# DM2097_CM4.net
KiCad netlist of a schematic drawn in Altium Designer
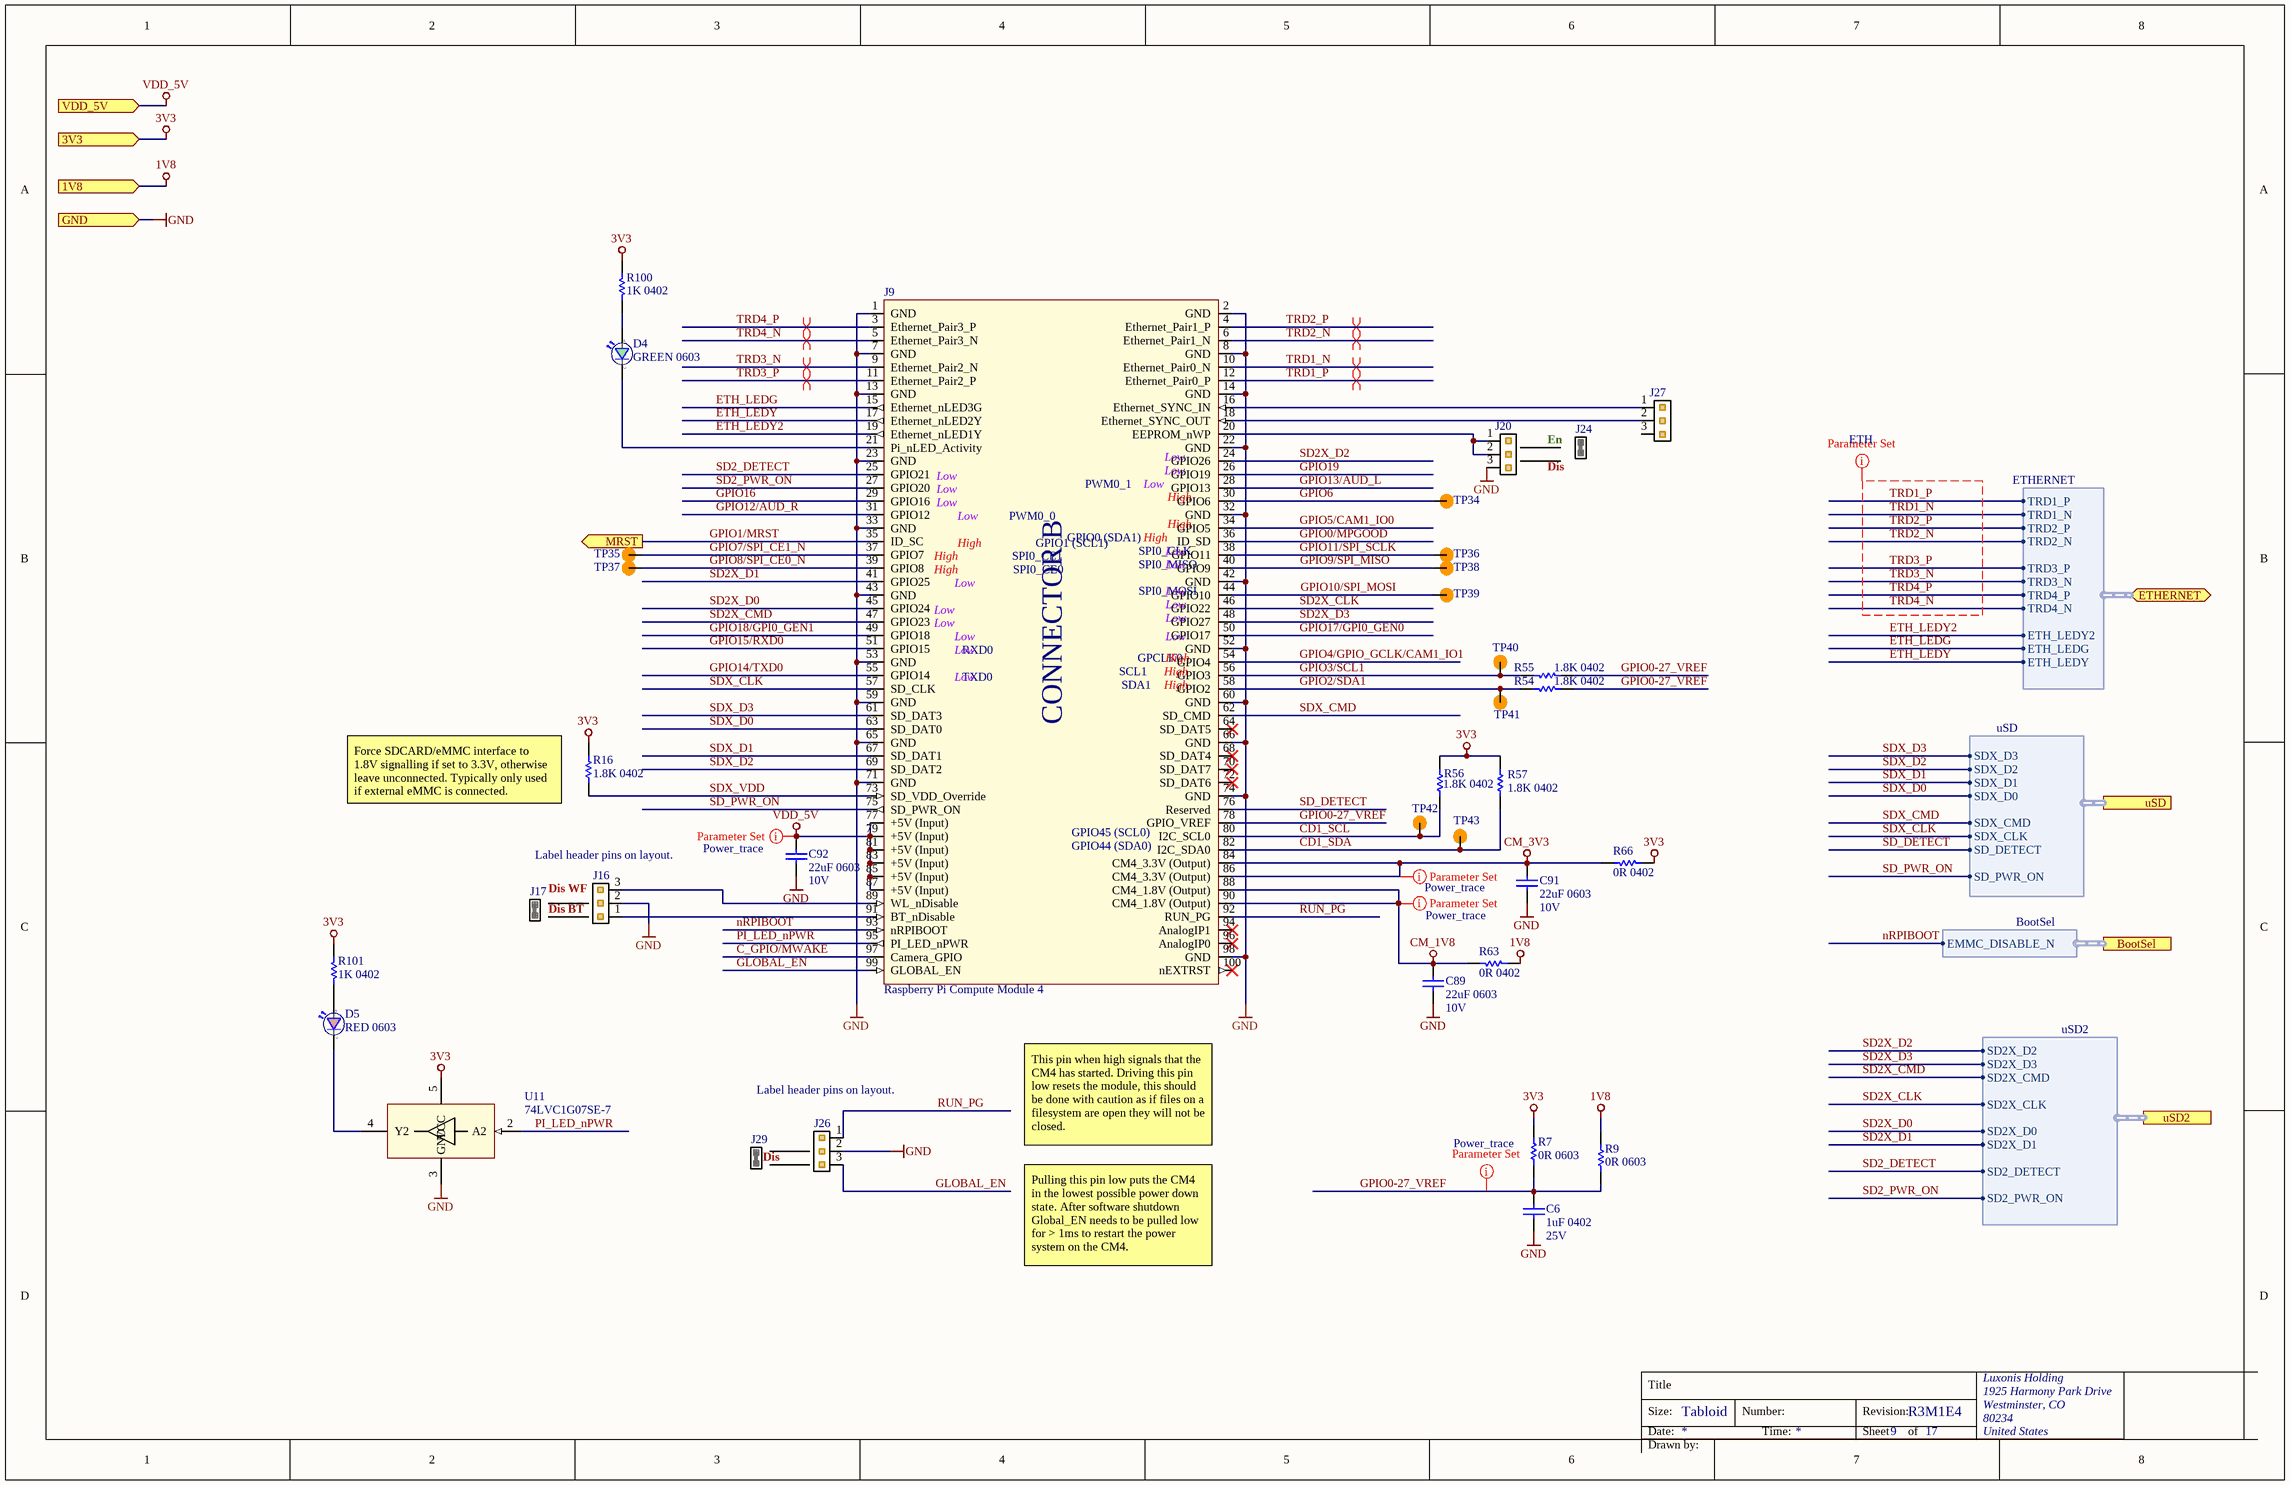
[diagram p0: DM2097_CM4.SchDoc]

(export (version "E")
  (design (tool "Eeschema 10.0.6"))
  (components
    (comp (ref "C6")
      (value "1uF 0402")
      (footprint "CAP_Altium_Vault_Generic:CAPC0402(1005)70_N")
      (description "CAP CER 1UF 25V X5R 0402 10%")
      (fields
        (field (name "TOLERANCE") "10%")
        (field (name "VOLTAGE") "25V")
        (field (name "VOLTAGE RATING") "25V")
      )
      (libsource (lib "LuxonisMaster") (part "GRM155R61E105KA12D"))
    )
    (comp (ref "C89")
      (value "22uF 0603")
      (footprint "CAP_Altium_Vault_Generic:CAPC0603(1608)100_N")
      (description "CAP CER 22UF 10V X5R 0603 20%")
      (fields (field (name "TOLERANCE") "20%") (field (name "VOLTAGE RATING") "10V"))
      (libsource (lib "LuxonisMaster") (part "GRM188R61A226ME15D"))
    )
    (comp (ref "C91")
      (value "22uF 0603")
      (footprint "CAP_Altium_Vault_Generic:CAPC0603(1608)100_N")
      (description "CAP CER 22UF 10V X5R 0603 20%")
      (fields (field (name "TOLERANCE") "20%") (field (name "VOLTAGE RATING") "10V"))
      (libsource (lib "LuxonisMaster") (part "GRM188R61A226ME15D"))
    )
    (comp (ref "C92")
      (value "22uF 0603")
      (footprint "CAP_Altium_Vault_Generic:CAPC0603(1608)100_N")
      (description "CAP CER 22UF 10V X5R 0603 20%")
      (fields (field (name "TOLERANCE") "20%") (field (name "VOLTAGE RATING") "10V"))
      (libsource (lib "LuxonisMaster") (part "GRM188R61A226ME15D"))
    )
    (comp (ref "D4")
      (value "GREEN 0603")
      (footprint "LuxonisMaster:SML_D1xx8W")
      (description "LED GREEN DIFFUSED 0603 SMD Green 572nm LED Indication - Discrete 2.2V 0603 (1608 Metric)")
      (fields (field (name "MANUFACTURER") "Rohm") (field (name "MANUFACTURER PART NUMBER") "SML-D12M8WT86"))
      (libsource (lib "LuxonisMaster") (part "SML-D12M8WT86"))
    )
    (comp (ref "D5")
      (value "RED 0603")
      (footprint "LuxonisMaster:SML_D1xx8W")
      (description "LED RED DIFFUSED 0603 SMD Red 620nm LED Indication - Discrete 2.2V 0603 (1608 Metric)")
      (libsource (lib "LuxonisMaster") (part "SML-D12U8WT86"))
    )
    (comp (ref "J9")
      (value "Raspberry Pi Compute Module 4")
      (footprint "CM4-Connector-B")
      (description "Raspberry Pi Compute Module 4 Hirose connector B")
      (libsource (lib "DM1097_SchLib") (part "CM4_CONNECTOR_B"))
    )
    (comp (ref "J16")
      (value "1.27MM PTH")
      (footprint "LuxonisMaster:GRPB031VWVN-RC")
      (description "CONN HEADER VERT 3POS 1.27MM")
      (libsource (lib "") (part "GRPB031VWVN-RC_1"))
    )
    (comp (ref "J17")
      (value "1.27mm hdr shunt")
      (footprint "LuxonisMaster:M50-1900005")
      (description "CONN SHUNT 1.27MM BLACK")
      (libsource (lib "LuxonisMaster") (part "M50-1900005"))
    )
    (comp (ref "J20")
      (value "1.27MM PTH")
      (footprint "LuxonisMaster:GRPB031VWVN-RC")
      (description "CONN HEADER VERT 3POS 1.27MM")
      (libsource (lib "LuxonisMaster") (part "GRPB031VWVN-RC"))
    )
    (comp (ref "J24")
      (value "1.27mm hdr shunt")
      (footprint "LuxonisMaster:M50-1900005")
      (description "CONN SHUNT 1.27MM BLACK")
      (libsource (lib "") (part "M50-1900005_1"))
    )
    (comp (ref "J26")
      (value "1.27MM PTH")
      (footprint "LuxonisMaster:GRPB031VWVN-RC")
      (description "CONN HEADER VERT 3POS 1.27MM")
      (libsource (lib "") (part "GRPB031VWVN-RC_2"))
    )
    (comp (ref "J27")
      (value "1.27MM PTH")
      (footprint "LuxonisMaster:GRPB031VWVN-RC")
      (description "CONN HEADER VERT 3POS 1.27MM")
      (libsource (lib "LuxonisMaster") (part "GRPB031VWVN-RC"))
    )
    (comp (ref "J29")
      (value "1.27mm hdr shunt")
      (footprint "LuxonisMaster:M50-1900005")
      (description "CONN SHUNT 1.27MM BLACK")
      (libsource (lib "LuxonisMaster") (part "M50-1900005"))
    )
    (comp (ref "R7")
      (value "0R 0603")
      (footprint "RES_Altium_Vault_Generic:RESC0603(1608)_N")
      (fields (field (name "TOLERANCE") "5%"))
      (libsource (lib "LuxonisMaster") (part "CRCW06030000Z0EA"))
    )
    (comp (ref "R9")
      (value "0R 0603")
      (footprint "RES_Altium_Vault_Generic:RESC0603(1608)_N")
      (fields (field (name "TOLERANCE") "5%"))
      (libsource (lib "LuxonisMaster") (part "CRCW06030000Z0EA"))
    )
    (comp (ref "R16")
      (value "1.8K 0402")
      (footprint "RES_Altium_Vault_Generic:RESC0402(1005)_N")
      (description "RES SMD 1.8K OHM 1% 1/16W 0402")
      (fields (field (name "TOLERANCE") "1%"))
      (libsource (lib "LuxonisMaster") (part "RC0402FR-071K8L"))
    )
    (comp (ref "R54")
      (value "1.8K 0402")
      (footprint "RES_Altium_Vault_Generic:RESC0402(1005)_N")
      (description "RES SMD 1.8K OHM 1% 1/16W 0402")
      (fields (field (name "TOLERANCE") "1%"))
      (libsource (lib "LuxonisMaster") (part "RC0402FR-071K8L"))
    )
    (comp (ref "R55")
      (value "1.8K 0402")
      (footprint "RES_Altium_Vault_Generic:RESC0402(1005)_N")
      (description "RES SMD 1.8K OHM 1% 1/16W 0402")
      (fields (field (name "TOLERANCE") "1%"))
      (libsource (lib "LuxonisMaster") (part "RC0402FR-071K8L"))
    )
    (comp (ref "R56")
      (value "1.8K 0402")
      (footprint "RES_Altium_Vault_Generic:RESC0402(1005)_N")
      (description "RES SMD 1.8K OHM 1% 1/16W 0402")
      (fields (field (name "TOLERANCE") "1%"))
      (libsource (lib "LuxonisMaster") (part "RC0402FR-071K8L"))
    )
    (comp (ref "R57")
      (value "1.8K 0402")
      (footprint "RES_Altium_Vault_Generic:RESC0402(1005)_N")
      (description "RES SMD 1.8K OHM 1% 1/16W 0402")
      (fields (field (name "TOLERANCE") "1%"))
      (libsource (lib "LuxonisMaster") (part "RC0402FR-071K8L"))
    )
    (comp (ref "R63")
      (value "0R 0402")
      (footprint "RES_Altium_Vault_Generic:RESC0402(1005)_N")
      (description "RES SMD 0 OHM JUMPER 1/16W 0402")
      (fields (field (name "TOLERANCE") "5%"))
      (libsource (lib "LuxonisMaster") (part "CRCW04020000Z0ED"))
    )
    (comp (ref "R66")
      (value "0R 0402")
      (footprint "RES_Altium_Vault_Generic:RESC0402(1005)_N")
      (description "RES SMD 0 OHM JUMPER 1/16W 0402")
      (fields (field (name "TOLERANCE") "5%"))
      (libsource (lib "LuxonisMaster") (part "CRCW04020000Z0ED"))
    )
    (comp (ref "R100")
      (value "1K 0402")
      (footprint "RES_Altium_Vault_Generic:RESC0402(1005)_N")
      (fields (field (name "TOLERANCE") "1%"))
      (libsource (lib "LuxonisMaster") (part "RC0402FR-071KL"))
    )
    (comp (ref "R101")
      (value "1K 0402")
      (footprint "RES_Altium_Vault_Generic:RESC0402(1005)_N")
      (fields (field (name "TOLERANCE") "1%"))
      (libsource (lib "LuxonisMaster") (part "RC0402FR-071KL"))
    )
    (comp (ref "TP34")
      (value "TP100_200_NS")
      (footprint "LuxonisMaster:TP100_200_NS")
      (libsource (lib "LuxonisMaster") (part "TEST_POINT"))
    )
    (comp (ref "TP35")
      (value "TP100_200_NS")
      (footprint "LuxonisMaster:TP100_200_NS")
      (libsource (lib "LuxonisMaster") (part "TEST_POINT"))
    )
    (comp (ref "TP36")
      (value "TP100_200_NS")
      (footprint "LuxonisMaster:TP100_200_NS")
      (libsource (lib "LuxonisMaster") (part "TEST_POINT"))
    )
    (comp (ref "TP37")
      (value "TP100_200_NS")
      (footprint "LuxonisMaster:TP100_200_NS")
      (libsource (lib "LuxonisMaster") (part "TEST_POINT"))
    )
    (comp (ref "TP38")
      (value "TP100_200_NS")
      (footprint "LuxonisMaster:TP100_200_NS")
      (libsource (lib "LuxonisMaster") (part "TEST_POINT"))
    )
    (comp (ref "TP39")
      (value "TP100_200_NS")
      (footprint "LuxonisMaster:TP100_200_NS")
      (libsource (lib "LuxonisMaster") (part "TEST_POINT"))
    )
    (comp (ref "TP40")
      (value "TP100_200_NS")
      (footprint "LuxonisMaster:TP100_200_NS")
      (libsource (lib "LuxonisMaster") (part "TEST_POINT"))
    )
    (comp (ref "TP41")
      (value "TP100_200_NS")
      (footprint "LuxonisMaster:TP100_200_NS")
      (libsource (lib "LuxonisMaster") (part "TEST_POINT"))
    )
    (comp (ref "TP42")
      (value "TP100_200_NS")
      (footprint "LuxonisMaster:TP100_200_NS")
      (libsource (lib "LuxonisMaster") (part "TEST_POINT"))
    )
    (comp (ref "TP43")
      (value "TP100_200_NS")
      (footprint "LuxonisMaster:TP100_200_NS")
      (libsource (lib "LuxonisMaster") (part "TEST_POINT"))
    )
    (comp (ref "U11")
      (value "74LVC1G07SE-7")
      (footprint "74LVC1G07SE-7")
      (description "SINGLE BUFFER/DRIVER WITH OPEN DRAIN OUTPUT")
      (libsource (lib "DM1097_SchLib") (part "74LVC1G07SE-7"))
    )
  )
  (nets
    (net (code "5") (name "/CD1_SCL") (class "Default")
      (node (ref "J9") (pin "80") (pinfunction "I2C_SCL0_80") (pintype "passive"))
      (node (ref "R56") (pin "1") (pinfunction "1_1") (pintype "passive"))
      (node (ref "TP42") (pin "1") (pintype "passive"))
    )
    (net (code "6") (name "/CD1_SDA") (class "Default")
      (node (ref "J9") (pin "82") (pinfunction "I2C_SDA0_82") (pintype "passive"))
      (node (ref "R57") (pin "1") (pinfunction "1_1") (pintype "passive"))
      (node (ref "TP43") (pin "1") (pintype "passive"))
    )
    (net (code "7") (name "/C_GPIO{slash}MWAKE") (class "Default")
      (node (ref "J9") (pin "97") (pinfunction "Camera_GPIO_97") (pintype "passive"))
    )
    (net (code "8") (name "/ETH_LEDG") (class "Default")
      (node (ref "J9") (pin "15") (pinfunction "Ethernet_nLED3G_15") (pintype "output"))
    )
    (net (code "9") (name "/ETH_LEDY") (class "Default")
      (node (ref "J9") (pin "17") (pinfunction "Ethernet_nLED2Y_17") (pintype "output"))
    )
    (net (code "10") (name "/ETH_LEDY2") (class "Default")
      (node (ref "J9") (pin "19") (pinfunction "Ethernet_nLED1Y_19") (pintype "output"))
    )
    (net (code "11") (name "/GLOBAL_EN") (class "Default")
      (node (ref "J26") (pin "3") (pinfunction "3_3") (pintype "passive"))
      (node (ref "J9") (pin "99") (pinfunction "GLOBAL_EN_99") (pintype "input"))
    )
    (net (code "12") (name "/GPIO0-27_VREF") (class "Default")
      (node (ref "C6") (pin "2") (pinfunction "2_2") (pintype "passive"))
      (node (ref "J9") (pin "78") (pinfunction "GPIO_VREF_78") (pintype "power_in"))
      (node (ref "R54") (pin "2") (pinfunction "2_2") (pintype "passive"))
      (node (ref "R55") (pin "2") (pinfunction "2_2") (pintype "passive"))
      (node (ref "R7") (pin "1") (pinfunction "1_1") (pintype "passive"))
      (node (ref "R9") (pin "1") (pinfunction "1_1") (pintype "passive"))
    )
    (net (code "13") (name "/GPIO0{slash}MPGOOD") (class "Default")
      (node (ref "J9") (pin "36") (pinfunction "ID_SD_36") (pintype "passive"))
    )
    (net (code "14") (name "/GPIO1{slash}MRST") (class "Default")
      (node (ref "J9") (pin "35") (pinfunction "ID_SC_35") (pintype "passive"))
    )
    (net (code "15") (name "/GPIO2{slash}SDA1") (class "Default")
      (node (ref "J9") (pin "58") (pinfunction "GPIO2_58") (pintype "passive"))
      (node (ref "R54") (pin "1") (pinfunction "1_1") (pintype "passive"))
      (node (ref "TP41") (pin "1") (pintype "passive"))
    )
    (net (code "16") (name "/GPIO3{slash}SCL1") (class "Default")
      (node (ref "J9") (pin "56") (pinfunction "GPIO3_56") (pintype "passive"))
      (node (ref "R55") (pin "1") (pinfunction "1_1") (pintype "passive"))
      (node (ref "TP40") (pin "1") (pintype "passive"))
    )
    (net (code "17") (name "/GPIO4{slash}GPIO_GCLK{slash}CAM1_IO1") (class "Default")
      (node (ref "J9") (pin "54") (pinfunction "GPIO4_54") (pintype "passive"))
    )
    (net (code "18") (name "/GPIO5{slash}CAM1_IO0") (class "Default")
      (node (ref "J9") (pin "34") (pinfunction "GPIO5_34") (pintype "passive"))
    )
    (net (code "19") (name "/GPIO6") (class "Default")
      (node (ref "J9") (pin "30") (pinfunction "GPIO6_30") (pintype "passive"))
      (node (ref "TP34") (pin "1") (pintype "passive"))
    )
    (net (code "20") (name "/GPIO7{slash}SPI_CE1_N") (class "Default")
      (node (ref "J9") (pin "37") (pinfunction "GPIO7_37") (pintype "passive"))
      (node (ref "TP35") (pin "1") (pintype "passive"))
    )
    (net (code "21") (name "/GPIO8{slash}SPI_CE0_N") (class "Default")
      (node (ref "J9") (pin "39") (pinfunction "GPIO8_39") (pintype "passive"))
      (node (ref "TP37") (pin "1") (pintype "passive"))
    )
    (net (code "22") (name "/GPIO9{slash}SPI_MISO") (class "Default")
      (node (ref "J9") (pin "40") (pinfunction "GPIO9_40") (pintype "passive"))
      (node (ref "TP38") (pin "1") (pintype "passive"))
    )
    (net (code "23") (name "/GPIO10{slash}SPI_MOSI") (class "Default")
      (node (ref "J9") (pin "44") (pinfunction "GPIO10_44") (pintype "passive"))
      (node (ref "TP39") (pin "1") (pintype "passive"))
    )
    (net (code "24") (name "/GPIO11{slash}SPI_SCLK") (class "Default")
      (node (ref "J9") (pin "38") (pinfunction "GPIO11_38") (pintype "passive"))
      (node (ref "TP36") (pin "1") (pintype "passive"))
    )
    (net (code "25") (name "/GPIO12{slash}AUD_R") (class "Default")
      (node (ref "J9") (pin "31") (pinfunction "GPIO12_31") (pintype "passive"))
    )
    (net (code "26") (name "/GPIO13{slash}AUD_L") (class "Default")
      (node (ref "J9") (pin "28") (pinfunction "GPIO13_28") (pintype "passive"))
    )
    (net (code "27") (name "/GPIO14{slash}TXD0") (class "Default")
      (node (ref "J9") (pin "55") (pinfunction "GPIO14_55") (pintype "passive"))
    )
    (net (code "28") (name "/GPIO15{slash}RXD0") (class "Default")
      (node (ref "J9") (pin "51") (pinfunction "GPIO15_51") (pintype "passive"))
    )
    (net (code "29") (name "/GPIO16") (class "Default")
      (node (ref "J9") (pin "29") (pinfunction "GPIO16_29") (pintype "passive"))
    )
    (net (code "30") (name "/GPIO17{slash}GPI0_GEN0") (class "Default")
      (node (ref "J9") (pin "50") (pinfunction "GPIO17_50") (pintype "passive"))
    )
    (net (code "31") (name "/GPIO18{slash}GPI0_GEN1") (class "Default")
      (node (ref "J9") (pin "49") (pinfunction "GPIO18_49") (pintype "passive"))
    )
    (net (code "32") (name "/GPIO19") (class "Default")
      (node (ref "J9") (pin "26") (pinfunction "GPIO19_26") (pintype "passive"))
    )
    (net (code "33") (name "/PI_LED_nPWR") (class "Default")
      (node (ref "J9") (pin "95") (pinfunction "PI_LED_nPWR_95") (pintype "output"))
      (node (ref "U11") (pin "2") (pinfunction "A2_2") (pintype "input"))
    )
    (net (code "34") (name "/RUN_PG") (class "Default")
      (node (ref "J26") (pin "1") (pinfunction "1_1") (pintype "passive"))
      (node (ref "J9") (pin "92") (pinfunction "RUN_PG_92") (pintype "passive"))
    )
    (net (code "35") (name "/SD2X_CLK") (class "Default")
      (node (ref "J9") (pin "46") (pinfunction "GPIO22_46") (pintype "passive"))
    )
    (net (code "36") (name "/SD2X_CMD") (class "Default")
      (node (ref "J9") (pin "47") (pinfunction "GPIO23_47") (pintype "passive"))
    )
    (net (code "37") (name "/SD2X_D0") (class "Default")
      (node (ref "J9") (pin "45") (pinfunction "GPIO24_45") (pintype "passive"))
    )
    (net (code "38") (name "/SD2X_D1") (class "Default")
      (node (ref "J9") (pin "41") (pinfunction "GPIO25_41") (pintype "passive"))
    )
    (net (code "39") (name "/SD2X_D2") (class "Default")
      (node (ref "J9") (pin "24") (pinfunction "GPIO26_24") (pintype "passive"))
    )
    (net (code "40") (name "/SD2X_D3") (class "Default")
      (node (ref "J9") (pin "48") (pinfunction "GPIO27_48") (pintype "passive"))
    )
    (net (code "41") (name "/SD2_DETECT") (class "Default")
      (node (ref "J9") (pin "25") (pinfunction "GPIO21_25") (pintype "passive"))
    )
    (net (code "42") (name "/SD2_PWR_ON") (class "Default")
      (node (ref "J9") (pin "27") (pinfunction "GPIO20_27") (pintype "passive"))
    )
    (net (code "43") (name "/SDX_CLK") (class "Default")
      (node (ref "J9") (pin "57") (pinfunction "SD_CLK_57") (pintype "passive"))
    )
    (net (code "44") (name "/SDX_CMD") (class "Default")
      (node (ref "J9") (pin "62") (pinfunction "SD_CMD_62") (pintype "passive"))
    )
    (net (code "45") (name "/SDX_D0") (class "Default")
      (node (ref "J9") (pin "63") (pinfunction "SD_DAT0_63") (pintype "passive"))
    )
    (net (code "46") (name "/SDX_D1") (class "Default")
      (node (ref "J9") (pin "67") (pinfunction "SD_DAT1_67") (pintype "passive"))
    )
    (net (code "47") (name "/SDX_D2") (class "Default")
      (node (ref "J9") (pin "69") (pinfunction "SD_DAT2_69") (pintype "passive"))
    )
    (net (code "48") (name "/SDX_D3") (class "Default")
      (node (ref "J9") (pin "61") (pinfunction "SD_DAT3_61") (pintype "passive"))
    )
    (net (code "49") (name "/SDX_VDD") (class "Default")
      (node (ref "J9") (pin "73") (pinfunction "SD_VDD_Override_73") (pintype "input"))
      (node (ref "R16") (pin "1") (pinfunction "1_1") (pintype "passive"))
    )
    (net (code "50") (name "/SD_DETECT") (class "Default")
      (node (ref "J9") (pin "76") (pinfunction "Reserved_76") (pintype "passive"))
    )
    (net (code "51") (name "/SD_PWR_ON") (class "Default")
      (node (ref "J9") (pin "75") (pinfunction "SD_PWR_ON_75") (pintype "output"))
    )
    (net (code "52") (name "/TRD1_N") (class "Default")
      (node (ref "J9") (pin "10") (pinfunction "Ethernet_Pair0_N_10") (pintype "passive"))
    )
    (net (code "53") (name "/TRD1_P") (class "Default")
      (node (ref "J9") (pin "12") (pinfunction "Ethernet_Pair0_P_12") (pintype "passive"))
    )
    (net (code "54") (name "/TRD2_N") (class "Default")
      (node (ref "J9") (pin "6") (pinfunction "Ethernet_Pair1_N_6") (pintype "passive"))
    )
    (net (code "55") (name "/TRD2_P") (class "Default")
      (node (ref "J9") (pin "4") (pinfunction "Ethernet_Pair1_P_4") (pintype "passive"))
    )
    (net (code "56") (name "/TRD3_N") (class "Default")
      (node (ref "J9") (pin "9") (pinfunction "Ethernet_Pair2_N_9") (pintype "passive"))
    )
    (net (code "57") (name "/TRD3_P") (class "Default")
      (node (ref "J9") (pin "11") (pinfunction "Ethernet_Pair2_P_11") (pintype "passive"))
    )
    (net (code "58") (name "/TRD4_N") (class "Default")
      (node (ref "J9") (pin "5") (pinfunction "Ethernet_Pair3_N_5") (pintype "passive"))
    )
    (net (code "59") (name "/TRD4_P") (class "Default")
      (node (ref "J9") (pin "3") (pinfunction "Ethernet_Pair3_P_3") (pintype "passive"))
    )
    (net (code "60") (name "/nRPIBOOT") (class "Default")
      (node (ref "J9") (pin "93") (pinfunction "nRPIBOOT_93") (pintype "input"))
    )
    (net (code "65") (name "1V8") (class "Default")
      (node (ref "R63") (pin "1") (pinfunction "1_1") (pintype "passive"))
      (node (ref "R9") (pin "2") (pinfunction "2_2") (pintype "passive"))
    )
    (net (code "66") (name "3V3") (class "Default")
      (node (ref "R100") (pin "2") (pinfunction "2_2") (pintype "passive"))
      (node (ref "R101") (pin "2") (pinfunction "2_2") (pintype "passive"))
      (node (ref "R16") (pin "2") (pinfunction "2_2") (pintype "passive"))
      (node (ref "R56") (pin "2") (pinfunction "2_2") (pintype "passive"))
      (node (ref "R57") (pin "2") (pinfunction "2_2") (pintype "passive"))
      (node (ref "R66") (pin "1") (pinfunction "1_1") (pintype "passive"))
      (node (ref "R7") (pin "2") (pinfunction "2_2") (pintype "passive"))
      (node (ref "U11") (pin "5") (pinfunction "VCC_5") (pintype "power_in"))
    )
    (net (code "67") (name "CM_1V8") (class "Default")
      (node (ref "C89") (pin "1") (pinfunction "1_1") (pintype "passive"))
      (node (ref "J9") (pin "88") (pinfunction "CM4_1.8V_(Output)_88") (pintype "power_in"))
      (node (ref "J9") (pin "90") (pinfunction "CM4_1.8V_(Output)_90") (pintype "power_in"))
      (node (ref "R63") (pin "2") (pinfunction "2_2") (pintype "passive"))
    )
    (net (code "68") (name "CM_3V3") (class "Default")
      (node (ref "C91") (pin "1") (pinfunction "1_1") (pintype "passive"))
      (node (ref "J9") (pin "84") (pinfunction "CM4_3.3V_(Output)_84") (pintype "power_in"))
      (node (ref "J9") (pin "86") (pinfunction "CM4_3.3V_(Output)_86") (pintype "power_in"))
      (node (ref "R66") (pin "2") (pinfunction "2_2") (pintype "passive"))
    )
    (net (code "69") (name "GND") (class "Default")
      (node (ref "C6") (pin "1") (pinfunction "1_1") (pintype "passive"))
      (node (ref "C89") (pin "2") (pinfunction "2_2") (pintype "passive"))
      (node (ref "C91") (pin "2") (pinfunction "2_2") (pintype "passive"))
      (node (ref "C92") (pin "2") (pinfunction "2_2") (pintype "passive"))
      (node (ref "J16") (pin "2") (pinfunction "2_2") (pintype "passive"))
      (node (ref "J20") (pin "3") (pinfunction "3_3") (pintype "passive"))
      (node (ref "J26") (pin "2") (pinfunction "2_2") (pintype "passive"))
      (node (ref "J9") (pin "1") (pinfunction "GND_1") (pintype "power_in"))
      (node (ref "J9") (pin "13") (pinfunction "GND_13") (pintype "power_in"))
      (node (ref "J9") (pin "14") (pinfunction "GND_14") (pintype "power_in"))
      (node (ref "J9") (pin "2") (pinfunction "GND_2") (pintype "power_in"))
      (node (ref "J9") (pin "22") (pinfunction "GND_22") (pintype "power_in"))
      (node (ref "J9") (pin "23") (pinfunction "GND_23") (pintype "power_in"))
      (node (ref "J9") (pin "32") (pinfunction "GND_32") (pintype "power_in"))
      (node (ref "J9") (pin "33") (pinfunction "GND_33") (pintype "power_in"))
      (node (ref "J9") (pin "42") (pinfunction "GND_42") (pintype "power_in"))
      (node (ref "J9") (pin "43") (pinfunction "GND_43") (pintype "power_in"))
      (node (ref "J9") (pin "52") (pinfunction "GND_52") (pintype "power_in"))
      (node (ref "J9") (pin "53") (pinfunction "GND_53") (pintype "power_in"))
      (node (ref "J9") (pin "59") (pinfunction "GND_59") (pintype "power_in"))
      (node (ref "J9") (pin "60") (pinfunction "GND_60") (pintype "power_in"))
      (node (ref "J9") (pin "65") (pinfunction "GND_65") (pintype "power_in"))
      (node (ref "J9") (pin "66") (pinfunction "GND_66") (pintype "power_in"))
      (node (ref "J9") (pin "7") (pinfunction "GND_7") (pintype "power_in"))
      (node (ref "J9") (pin "71") (pinfunction "GND_71") (pintype "power_in"))
      (node (ref "J9") (pin "74") (pinfunction "GND_74") (pintype "power_in"))
      (node (ref "J9") (pin "8") (pinfunction "GND_8") (pintype "power_in"))
      (node (ref "J9") (pin "98") (pinfunction "GND_98") (pintype "power_in"))
      (node (ref "U11") (pin "3") (pinfunction "GND_3") (pintype "power_in"))
    )
    (net (code "70") (name "Net-(D4-A)") (class "Default")
      (node (ref "D4") (pin "2") (pinfunction "A_2") (pintype "passive"))
      (node (ref "R100") (pin "1") (pinfunction "1_1") (pintype "passive"))
    )
    (net (code "71") (name "Net-(D4-C)") (class "Default")
      (node (ref "D4") (pin "1") (pinfunction "C_1") (pintype "passive"))
      (node (ref "J9") (pin "21") (pinfunction "Pi_nLED_Activity_21") (pintype "open_collector"))
    )
    (net (code "72") (name "Net-(D5-A)") (class "Default")
      (node (ref "D5") (pin "2") (pinfunction "A_2") (pintype "passive"))
      (node (ref "R101") (pin "1") (pinfunction "1_1") (pintype "passive"))
    )
    (net (code "73") (name "Net-(D5-C)") (class "Default")
      (node (ref "D5") (pin "1") (pinfunction "C_1") (pintype "passive"))
      (node (ref "U11") (pin "4") (pinfunction "Y2_4") (pintype "open_collector"))
    )
    (net (code "74") (name "Net-(J9-BT_nDisable)") (class "Default")
      (node (ref "J16") (pin "1") (pinfunction "1_1") (pintype "passive"))
      (node (ref "J9") (pin "91") (pinfunction "BT_nDisable_91") (pintype "input"))
    )
    (net (code "75") (name "Net-(J9-EEPROM_nWP)") (class "Default")
      (node (ref "J20") (pin "1") (pinfunction "1_1") (pintype "passive"))
      (node (ref "J20") (pin "2") (pinfunction "2_2") (pintype "passive"))
      (node (ref "J9") (pin "20") (pinfunction "EEPROM_nWP_20") (pintype "passive"))
    )
    (net (code "76") (name "Net-(J9-Ethernet_SYNC_IN)") (class "Default")
      (node (ref "J27") (pin "1") (pinfunction "1_1") (pintype "passive"))
      (node (ref "J9") (pin "16") (pinfunction "Ethernet_SYNC_IN_16") (pintype "input"))
    )
    (net (code "77") (name "Net-(J9-Ethernet_SYNC_OUT)") (class "Default")
      (node (ref "J27") (pin "2") (pinfunction "2_2") (pintype "passive"))
      (node (ref "J9") (pin "18") (pinfunction "Ethernet_SYNC_OUT_18") (pintype "input"))
    )
    (net (code "78") (name "Net-(J9-WL_nDisable)") (class "Default")
      (node (ref "J16") (pin "3") (pinfunction "3_3") (pintype "passive"))
      (node (ref "J9") (pin "89") (pinfunction "WL_nDisable_89") (pintype "input"))
    )
    (net (code "79") (name "VDD_5V") (class "Default")
      (node (ref "C92") (pin "1") (pinfunction "1_1") (pintype "passive"))
      (node (ref "J9") (pin "77") (pinfunction "+5V_(Input)_77") (pintype "power_in"))
      (node (ref "J9") (pin "79") (pinfunction "+5V_(Input)_79") (pintype "power_in"))
      (node (ref "J9") (pin "81") (pinfunction "+5V_(Input)_81") (pintype "power_in"))
      (node (ref "J9") (pin "83") (pinfunction "+5V_(Input)_83") (pintype "power_in"))
      (node (ref "J9") (pin "85") (pinfunction "+5V_(Input)_85") (pintype "power_in"))
      (node (ref "J9") (pin "87") (pinfunction "+5V_(Input)_87") (pintype "power_in"))
    )
    (net (code "80") (name "unconnected-(J9-AnalogIP0-Pad96)") (class "Default")
      (node (ref "J9") (pin "96") (pinfunction "AnalogIP0_96") (pintype "passive+no_connect"))
    )
    (net (code "81") (name "unconnected-(J9-AnalogIP1-Pad94)") (class "Default")
      (node (ref "J9") (pin "94") (pinfunction "AnalogIP1_94") (pintype "passive+no_connect"))
    )
    (net (code "82") (name "unconnected-(J9-SD_DAT4-Pad68)") (class "Default")
      (node (ref "J9") (pin "68") (pinfunction "SD_DAT4_68") (pintype "passive+no_connect"))
    )
    (net (code "83") (name "unconnected-(J9-SD_DAT5-Pad64)") (class "Default")
      (node (ref "J9") (pin "64") (pinfunction "SD_DAT5_64") (pintype "passive+no_connect"))
    )
    (net (code "84") (name "unconnected-(J9-SD_DAT6-Pad72)") (class "Default")
      (node (ref "J9") (pin "72") (pinfunction "SD_DAT6_72") (pintype "passive+no_connect"))
    )
    (net (code "85") (name "unconnected-(J9-SD_DAT7-Pad70)") (class "Default")
      (node (ref "J9") (pin "70") (pinfunction "SD_DAT7_70") (pintype "passive+no_connect"))
    )
    (net (code "86") (name "unconnected-(J9-nEXTRST-Pad100)") (class "Default")
      (node (ref "J9") (pin "100") (pinfunction "nEXTRST_100") (pintype "output+no_connect"))
    )
    (net (code "87") (name "unconnected-(J27-Pad3)") (class "Default")
      (node (ref "J27") (pin "3") (pinfunction "3_3") (pintype "passive"))
    )
  )
)
